# blinkm_mk2m.net
KiCad netlist of a schematic drawn in EAGLE
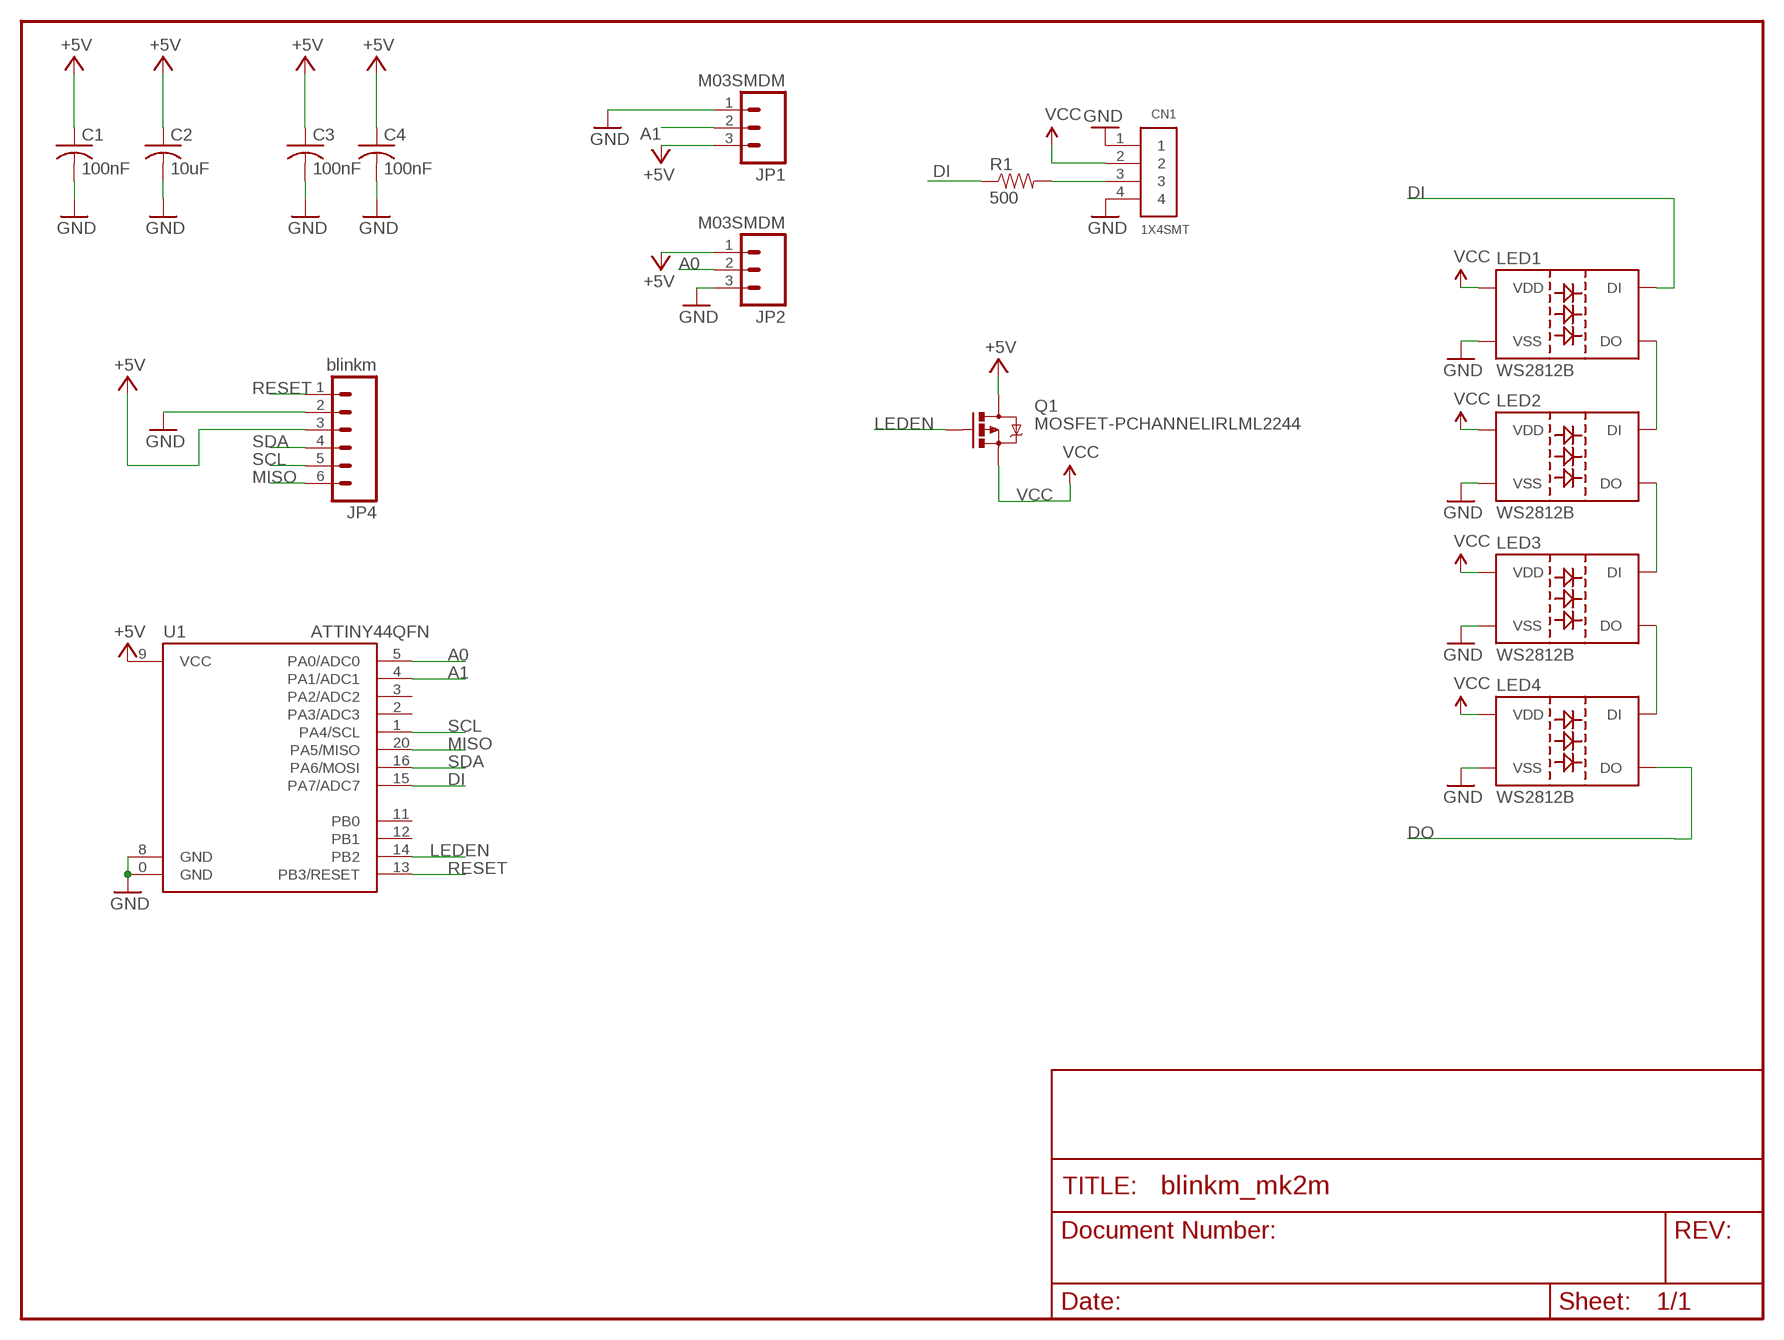
[diagram p0: schematic, sheet 1]

(export (version "E")
  (design (tool "Eeschema 10.0.6"))
  (components
    (comp (ref "C1")
      (value "100nF")
      (footprint "eagle-import:C0603")
      (libsource (lib "eagle-import") (part "C-USC0603"))
    )
    (comp (ref "C2")
      (value "10uF")
      (footprint "eagle-import:C0603")
      (libsource (lib "eagle-import") (part "C-USC0603"))
    )
    (comp (ref "C3")
      (value "100nF")
      (footprint "eagle-import:C0603")
      (libsource (lib "eagle-import") (part "C-USC0603"))
    )
    (comp (ref "C4")
      (value "100nF")
      (footprint "eagle-import:C0603")
      (libsource (lib "eagle-import") (part "C-USC0603"))
    )
    (comp (ref "CN1")
      (value "1X4SMT")
      (footprint "eagle-import:1X4-SMT")
      (libsource (lib "eagle-import") (part "1X4SMT"))
    )
    (comp (ref "JP1")
      (value "M03SMDM")
      (footprint "eagle-import:1X03-SMD-MINIMAL")
      (libsource (lib "eagle-import") (part "M03SMDM"))
    )
    (comp (ref "JP2")
      (value "M03SMDM")
      (footprint "eagle-import:1X03-SMD-MINIMAL")
      (libsource (lib "eagle-import") (part "M03SMDM"))
    )
    (comp (ref "JP4")
      (value "blinkm")
      (footprint "eagle-import:1X06_LOCK")
      (libsource (lib "eagle-import") (part "M06LOCK"))
    )
    (comp (ref "LED1")
      (value "WS2812B")
      (footprint "eagle-import:WS2812B")
      (libsource (lib "eagle-import") (part "WS2812B"))
    )
    (comp (ref "LED2")
      (value "WS2812B")
      (footprint "eagle-import:WS2812B")
      (libsource (lib "eagle-import") (part "WS2812B"))
    )
    (comp (ref "LED3")
      (value "WS2812B")
      (footprint "eagle-import:WS2812B")
      (libsource (lib "eagle-import") (part "WS2812B"))
    )
    (comp (ref "LED4")
      (value "WS2812B")
      (footprint "eagle-import:WS2812B")
      (libsource (lib "eagle-import") (part "WS2812B"))
    )
    (comp (ref "Q1")
      (value "MOSFET-PCHANNELIRLML2244")
      (footprint "eagle-import:SOT23-3")
      (libsource (lib "eagle-import") (part "MOSFET-PCHANNELIRLML2244"))
    )
    (comp (ref "R1")
      (value "500")
      (footprint "eagle-import:0603-RES")
      (libsource (lib "eagle-import") (part "RESISTOR0603"))
    )
    (comp (ref "U1")
      (value "ATTINY44QFN")
      (footprint "eagle-import:QFN20")
      (libsource (lib "eagle-import") (part "ATTINY24QFN"))
    )
  )
  (nets
    (net (code "1") (name "+5V") (class "Default")
      (node (ref "C1") (pin "1") (pinfunction "1_1") (pintype "passive"))
      (node (ref "C2") (pin "1") (pinfunction "1_1") (pintype "passive"))
      (node (ref "C3") (pin "1") (pinfunction "1_1") (pintype "passive"))
      (node (ref "C4") (pin "1") (pinfunction "1_1") (pintype "passive"))
      (node (ref "JP1") (pin "3") (pinfunction "3_3") (pintype "passive"))
      (node (ref "JP2") (pin "1") (pinfunction "1_1") (pintype "passive"))
      (node (ref "JP4") (pin "3") (pinfunction "3_3") (pintype "passive"))
      (node (ref "Q1") (pin "3") (pinfunction "D_3") (pintype "passive"))
      (node (ref "U1") (pin "9") (pinfunction "VCC_9") (pintype "bidirectional"))
    )
    (net (code "2") (name "/A0") (class "Default")
      (node (ref "JP2") (pin "2") (pinfunction "2_2") (pintype "passive"))
      (node (ref "U1") (pin "5") (pinfunction "PA0/ADC0_5") (pintype "bidirectional"))
    )
    (net (code "3") (name "/A1") (class "Default")
      (node (ref "JP1") (pin "2") (pinfunction "2_2") (pintype "passive"))
      (node (ref "U1") (pin "4") (pinfunction "PA1/ADC1_4") (pintype "bidirectional"))
    )
    (net (code "4") (name "/DI") (class "Default")
      (node (ref "LED1") (pin "4") (pinfunction "DI_4") (pintype "bidirectional"))
      (node (ref "R1") (pin "1") (pinfunction "1_1") (pintype "passive"))
      (node (ref "U1") (pin "15") (pinfunction "PA7/ADC7_15") (pintype "bidirectional"))
    )
    (net (code "5") (name "/DO") (class "Default")
      (node (ref "LED4") (pin "2") (pinfunction "DO_2") (pintype "bidirectional"))
    )
    (net (code "6") (name "/LEDEN") (class "Default")
      (node (ref "Q1") (pin "1") (pinfunction "G_1") (pintype "passive"))
      (node (ref "U1") (pin "14") (pinfunction "PB2_14") (pintype "bidirectional"))
    )
    (net (code "7") (name "/MISO") (class "Default")
      (node (ref "JP4") (pin "6") (pinfunction "6_6") (pintype "passive"))
      (node (ref "U1") (pin "20") (pinfunction "PA5/MISO_20") (pintype "bidirectional"))
    )
    (net (code "8") (name "/RESET") (class "Default")
      (node (ref "JP4") (pin "1") (pinfunction "1_1") (pintype "passive"))
      (node (ref "U1") (pin "13") (pinfunction "PB3/RESET_13") (pintype "bidirectional"))
    )
    (net (code "9") (name "/SCL") (class "Default")
      (node (ref "JP4") (pin "5") (pinfunction "5_5") (pintype "passive"))
      (node (ref "U1") (pin "1") (pinfunction "PA4/SCL_1") (pintype "bidirectional"))
    )
    (net (code "10") (name "/SDA") (class "Default")
      (node (ref "JP4") (pin "4") (pinfunction "4_4") (pintype "passive"))
      (node (ref "U1") (pin "16") (pinfunction "PA6/MOSI_16") (pintype "bidirectional"))
    )
    (net (code "11") (name "GND") (class "Default")
      (node (ref "C1") (pin "2") (pinfunction "2_2") (pintype "passive"))
      (node (ref "C2") (pin "2") (pinfunction "2_2") (pintype "passive"))
      (node (ref "C3") (pin "2") (pinfunction "2_2") (pintype "passive"))
      (node (ref "C4") (pin "2") (pinfunction "2_2") (pintype "passive"))
      (node (ref "CN1") (pin "1") (pinfunction "1_1") (pintype "bidirectional"))
      (node (ref "CN1") (pin "4") (pinfunction "4_4") (pintype "bidirectional"))
      (node (ref "JP1") (pin "1") (pinfunction "1_1") (pintype "passive"))
      (node (ref "JP2") (pin "3") (pinfunction "3_3") (pintype "passive"))
      (node (ref "JP4") (pin "2") (pinfunction "2_2") (pintype "passive"))
      (node (ref "LED1") (pin "3") (pinfunction "VSS_3") (pintype "bidirectional"))
      (node (ref "LED2") (pin "3") (pinfunction "VSS_3") (pintype "bidirectional"))
      (node (ref "LED3") (pin "3") (pinfunction "VSS_3") (pintype "bidirectional"))
      (node (ref "LED4") (pin "3") (pinfunction "VSS_3") (pintype "bidirectional"))
      (node (ref "U1") (pin "0") (pinfunction "GND_0") (pintype "bidirectional"))
      (node (ref "U1") (pin "8") (pinfunction "GND_8") (pintype "bidirectional"))
    )
    (net (code "12") (name "Net-(CN1-Pad3)") (class "Default")
      (node (ref "CN1") (pin "3") (pinfunction "3_3") (pintype "bidirectional"))
      (node (ref "R1") (pin "2") (pinfunction "2_2") (pintype "passive"))
    )
    (net (code "13") (name "Net-(LED1-DO)") (class "Default")
      (node (ref "LED1") (pin "2") (pinfunction "DO_2") (pintype "bidirectional"))
      (node (ref "LED2") (pin "4") (pinfunction "DI_4") (pintype "bidirectional"))
    )
    (net (code "14") (name "Net-(LED2-DO)") (class "Default")
      (node (ref "LED2") (pin "2") (pinfunction "DO_2") (pintype "bidirectional"))
      (node (ref "LED3") (pin "4") (pinfunction "DI_4") (pintype "bidirectional"))
    )
    (net (code "15") (name "Net-(LED3-DO)") (class "Default")
      (node (ref "LED3") (pin "2") (pinfunction "DO_2") (pintype "bidirectional"))
      (node (ref "LED4") (pin "4") (pinfunction "DI_4") (pintype "bidirectional"))
    )
    (net (code "16") (name "VCC") (class "Default")
      (node (ref "CN1") (pin "2") (pinfunction "2_2") (pintype "bidirectional"))
      (node (ref "LED1") (pin "1") (pinfunction "VDD_1") (pintype "bidirectional"))
      (node (ref "LED2") (pin "1") (pinfunction "VDD_1") (pintype "bidirectional"))
      (node (ref "LED3") (pin "1") (pinfunction "VDD_1") (pintype "bidirectional"))
      (node (ref "LED4") (pin "1") (pinfunction "VDD_1") (pintype "bidirectional"))
      (node (ref "Q1") (pin "2") (pinfunction "S_2") (pintype "passive"))
    )
    (net (code "17") (name "unconnected-(U1-PA2{slash}ADC2-Pad3)") (class "Default")
      (node (ref "U1") (pin "3") (pinfunction "PA2/ADC2_3") (pintype "bidirectional"))
    )
    (net (code "18") (name "unconnected-(U1-PA3{slash}ADC3-Pad2)") (class "Default")
      (node (ref "U1") (pin "2") (pinfunction "PA3/ADC3_2") (pintype "bidirectional"))
    )
    (net (code "19") (name "unconnected-(U1-PB0-Pad11)") (class "Default")
      (node (ref "U1") (pin "11") (pinfunction "PB0_11") (pintype "bidirectional"))
    )
    (net (code "20") (name "unconnected-(U1-PB1-Pad12)") (class "Default")
      (node (ref "U1") (pin "12") (pinfunction "PB1_12") (pintype "bidirectional"))
    )
  )
)
